# CV_Mode.net
KiCad netlist of a schematic drawn in Altium Designer
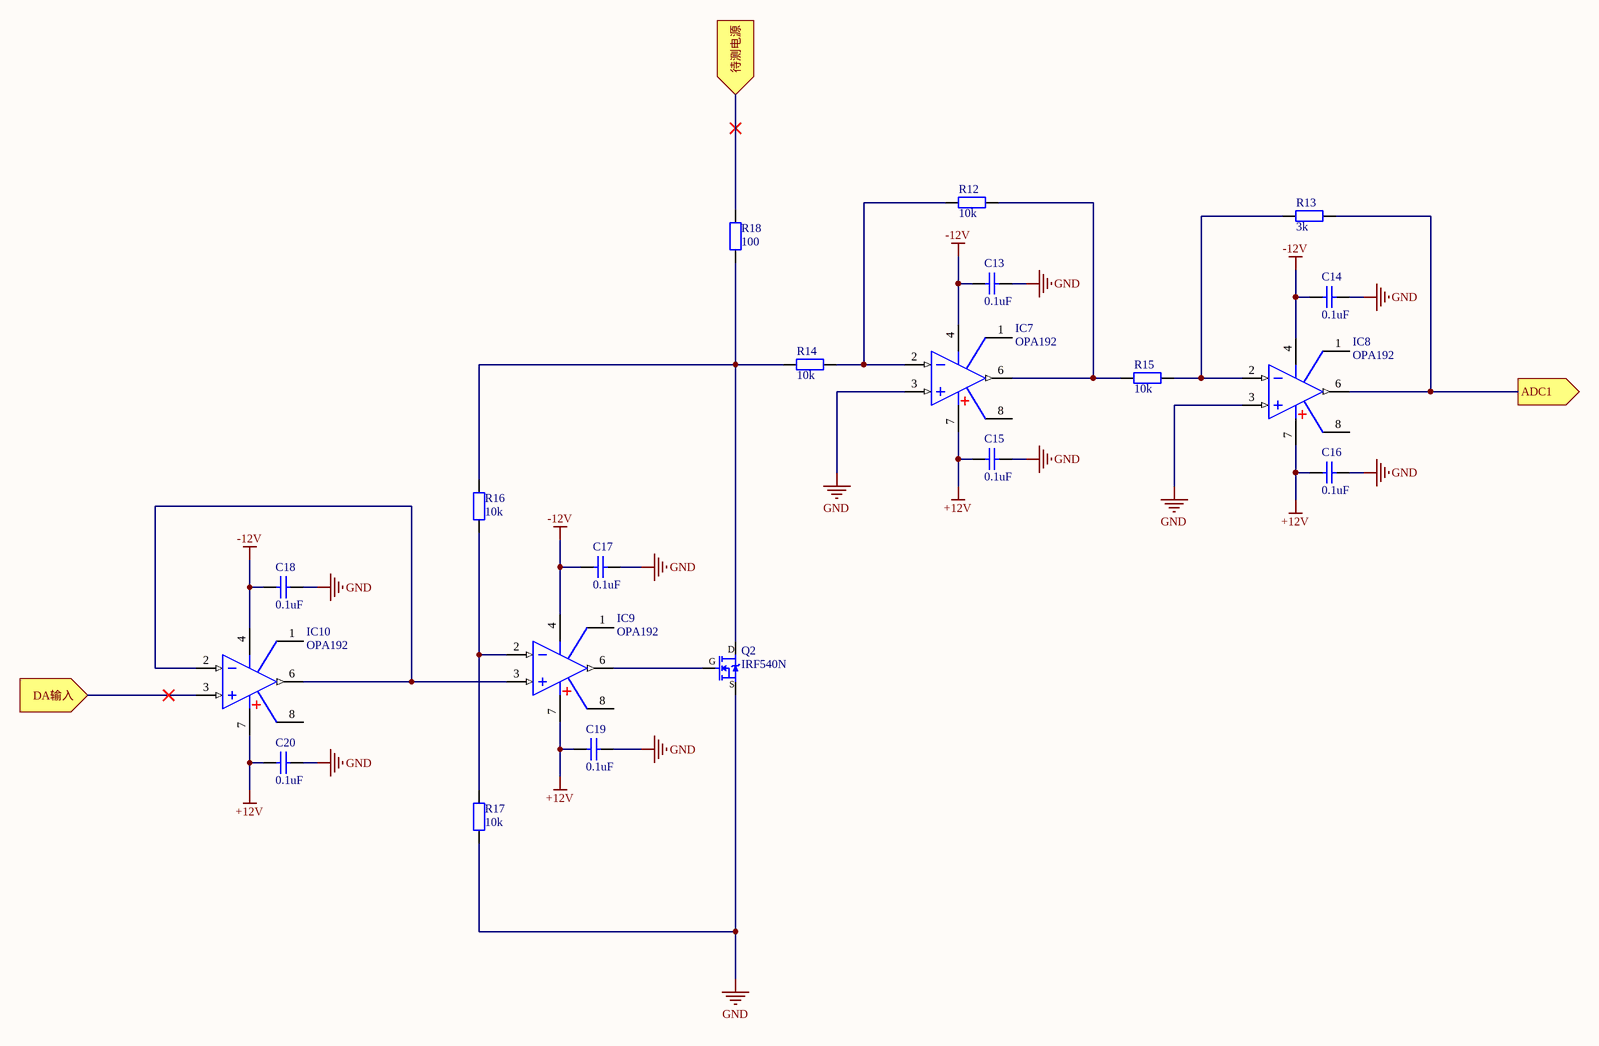
[diagram p0: CV_Mode.SchDoc]

(export (version "E")
  (design (tool "Eeschema 10.0.6"))
  (components
    (comp (ref "C13")
      (value "0.1uF")
      (footprint "瓷片电容")
      (description "直插电容")
      (fields (field (name "VOLTAGE") "63V") (field (name "PUBLISHER") "Altium Limited"))
      (libsource (lib "My_Intlib") (part "Cap_DIP"))
    )
    (comp (ref "C14")
      (value "0.1uF")
      (footprint "瓷片电容")
      (description "直插电容")
      (fields (field (name "VOLTAGE") "63V") (field (name "PUBLISHER") "Altium Limited"))
      (libsource (lib "My_Intlib") (part "Cap_DIP"))
    )
    (comp (ref "C15")
      (value "0.1uF")
      (footprint "瓷片电容")
      (description "直插电容")
      (fields (field (name "VOLTAGE") "63V") (field (name "PUBLISHER") "Altium Limited"))
      (libsource (lib "My_Intlib") (part "Cap_DIP"))
    )
    (comp (ref "C16")
      (value "0.1uF")
      (footprint "瓷片电容")
      (description "直插电容")
      (fields (field (name "VOLTAGE") "63V") (field (name "PUBLISHER") "Altium Limited"))
      (libsource (lib "My_Intlib") (part "Cap_DIP"))
    )
    (comp (ref "C17")
      (value "0.1uF")
      (footprint "瓷片电容")
      (description "直插电容")
      (fields (field (name "VOLTAGE") "63V") (field (name "PUBLISHER") "Altium Limited"))
      (libsource (lib "My_Intlib") (part "Cap_DIP"))
    )
    (comp (ref "C18")
      (value "0.1uF")
      (footprint "瓷片电容")
      (description "直插电容")
      (fields (field (name "VOLTAGE") "63V") (field (name "PUBLISHER") "Altium Limited"))
      (libsource (lib "My_Intlib") (part "Cap_DIP"))
    )
    (comp (ref "C19")
      (value "0.1uF")
      (footprint "瓷片电容")
      (description "直插电容")
      (fields (field (name "VOLTAGE") "63V") (field (name "PUBLISHER") "Altium Limited"))
      (libsource (lib "My_Intlib") (part "Cap_DIP"))
    )
    (comp (ref "C20")
      (value "0.1uF")
      (footprint "瓷片电容")
      (description "直插电容")
      (fields (field (name "VOLTAGE") "63V") (field (name "PUBLISHER") "Altium Limited"))
      (libsource (lib "My_Intlib") (part "Cap_DIP"))
    )
    (comp (ref "IC7")
      (value "OPA192")
      (footprint "SOP8_N")
      (description "High-Voltage, Rail-to-Rail Input/Output, 5µV, 0.2µV/˚C, Precision Operational Amplifier")
      (fields (field (name "版权归属") "源创客"))
      (libsource (lib "My_Intlib") (part "OPA192"))
    )
    (comp (ref "IC8")
      (value "OPA192")
      (footprint "SOP8_N")
      (description "High-Voltage, Rail-to-Rail Input/Output, 5µV, 0.2µV/˚C, Precision Operational Amplifier")
      (fields (field (name "版权归属") "源创客"))
      (libsource (lib "My_Intlib") (part "OPA192"))
    )
    (comp (ref "IC9")
      (value "OPA192")
      (footprint "SOP8_N")
      (description "High-Voltage, Rail-to-Rail Input/Output, 5µV, 0.2µV/˚C, Precision Operational Amplifier")
      (fields (field (name "版权归属") "源创客"))
      (libsource (lib "My_Intlib") (part "OPA192"))
    )
    (comp (ref "IC10")
      (value "OPA192")
      (footprint "SOP8_N")
      (description "High-Voltage, Rail-to-Rail Input/Output, 5µV, 0.2µV/˚C, Precision Operational Amplifier")
      (fields (field (name "版权归属") "源创客"))
      (libsource (lib "My_Intlib") (part "OPA192"))
    )
    (comp (ref "Q2")
      (value "IRF540N")
      (footprint "TO263-3B")
      (description "N沟场 100V/22A")
      (fields (field (name "版权归属") "源创客"))
      (libsource (lib "My_Intlib") (part "IRF540N"))
    )
    (comp (ref "R12")
      (value "10k")
      (footprint "RS 1/4W")
      (description "直插电阻")
      (libsource (lib "") (part "Res_DIP_1"))
    )
    (comp (ref "R13")
      (value "3k")
      (footprint "RS 1/4W")
      (description "直插电阻")
      (libsource (lib "") (part "Res_DIP_1"))
    )
    (comp (ref "R14")
      (value "10k")
      (footprint "RS 1/4W")
      (description "直插电阻")
      (libsource (lib "") (part "Res_DIP_1"))
    )
    (comp (ref "R15")
      (value "10k")
      (footprint "RS 1/4W")
      (description "直插电阻")
      (libsource (lib "") (part "Res_DIP_1"))
    )
    (comp (ref "R16")
      (value "10k")
      (footprint "RS 1/4W")
      (description "直插电阻")
      (libsource (lib "My_Intlib") (part "Res_DIP"))
    )
    (comp (ref "R17")
      (value "10k")
      (footprint "RS 1/4W")
      (description "直插电阻")
      (libsource (lib "My_Intlib") (part "Res_DIP"))
    )
    (comp (ref "R18")
      (value "100")
      (footprint "RS 1/4W")
      (description "直插电阻")
      (libsource (lib "My_Intlib") (part "Res_DIP"))
    )
  )
  (nets
    (net (code "1") (name "+12V") (class "Default")
      (node (ref "C15") (pin "1") (pinfunction "1_1") (pintype "passive"))
      (node (ref "C16") (pin "1") (pinfunction "1_1") (pintype "passive"))
      (node (ref "C19") (pin "1") (pinfunction "1_1") (pintype "passive"))
      (node (ref "C20") (pin "1") (pinfunction "1_1") (pintype "passive"))
      (node (ref "IC10") (pin "7") (pinfunction "V+_7") (pintype "power_in"))
      (node (ref "IC7") (pin "7") (pinfunction "V+_7") (pintype "power_in"))
      (node (ref "IC8") (pin "7") (pinfunction "V+_7") (pintype "power_in"))
      (node (ref "IC9") (pin "7") (pinfunction "V+_7") (pintype "power_in"))
    )
    (net (code "2") (name "-12V") (class "Default")
      (node (ref "C13") (pin "1") (pinfunction "1_1") (pintype "passive"))
      (node (ref "C14") (pin "1") (pinfunction "1_1") (pintype "passive"))
      (node (ref "C17") (pin "1") (pinfunction "1_1") (pintype "passive"))
      (node (ref "C18") (pin "1") (pinfunction "1_1") (pintype "passive"))
      (node (ref "IC10") (pin "4") (pinfunction "V-_4") (pintype "power_in"))
      (node (ref "IC7") (pin "4") (pinfunction "V-_4") (pintype "power_in"))
      (node (ref "IC8") (pin "4") (pinfunction "V-_4") (pintype "power_in"))
      (node (ref "IC9") (pin "4") (pinfunction "V-_4") (pintype "power_in"))
    )
    (net (code "3") (name "/ADC1") (class "Default")
      (node (ref "IC8") (pin "6") (pinfunction "OUT_6") (pintype "output"))
      (node (ref "R13") (pin "2") (pinfunction "2_2") (pintype "passive"))
    )
    (net (code "4") (name "/DA输入") (class "Default")
      (node (ref "IC10") (pin "3") (pinfunction "IN+_3") (pintype "input"))
    )
    (net (code "5") (name "/待测电源") (class "Default")
      (node (ref "R18") (pin "2") (pinfunction "2_2") (pintype "passive"))
    )
    (net (code "6") (name "GND") (class "Default")
      (node (ref "C13") (pin "2") (pinfunction "2_2") (pintype "passive"))
      (node (ref "C14") (pin "2") (pinfunction "2_2") (pintype "passive"))
      (node (ref "C15") (pin "2") (pinfunction "2_2") (pintype "passive"))
      (node (ref "C16") (pin "2") (pinfunction "2_2") (pintype "passive"))
      (node (ref "C17") (pin "2") (pinfunction "2_2") (pintype "passive"))
      (node (ref "C18") (pin "2") (pinfunction "2_2") (pintype "passive"))
      (node (ref "C19") (pin "2") (pinfunction "2_2") (pintype "passive"))
      (node (ref "C20") (pin "2") (pinfunction "2_2") (pintype "passive"))
      (node (ref "IC7") (pin "3") (pinfunction "IN+_3") (pintype "input"))
      (node (ref "IC8") (pin "3") (pinfunction "IN+_3") (pintype "input"))
      (node (ref "Q2") (pin "3") (pinfunction "D_3") (pintype "passive"))
      (node (ref "R17") (pin "1") (pinfunction "1_1") (pintype "passive"))
    )
    (net (code "7") (name "Net-(IC7-IN-)") (class "Default")
      (node (ref "IC7") (pin "2") (pinfunction "IN-_2") (pintype "input"))
      (node (ref "R12") (pin "1") (pinfunction "1_1") (pintype "passive"))
      (node (ref "R14") (pin "2") (pinfunction "2_2") (pintype "passive"))
    )
    (net (code "8") (name "Net-(IC7-OUT)") (class "Default")
      (node (ref "IC7") (pin "6") (pinfunction "OUT_6") (pintype "output"))
      (node (ref "R12") (pin "2") (pinfunction "2_2") (pintype "passive"))
      (node (ref "R15") (pin "1") (pinfunction "1_1") (pintype "passive"))
    )
    (net (code "9") (name "Net-(IC8-IN-)") (class "Default")
      (node (ref "IC8") (pin "2") (pinfunction "IN-_2") (pintype "input"))
      (node (ref "R13") (pin "1") (pinfunction "1_1") (pintype "passive"))
      (node (ref "R15") (pin "2") (pinfunction "2_2") (pintype "passive"))
    )
    (net (code "10") (name "Net-(IC9-IN-)") (class "Default")
      (node (ref "IC9") (pin "2") (pinfunction "IN-_2") (pintype "input"))
      (node (ref "R16") (pin "1") (pinfunction "1_1") (pintype "passive"))
      (node (ref "R17") (pin "2") (pinfunction "2_2") (pintype "passive"))
    )
    (net (code "11") (name "Net-(IC9-OUT)") (class "Default")
      (node (ref "IC9") (pin "6") (pinfunction "OUT_6") (pintype "output"))
      (node (ref "Q2") (pin "1") (pinfunction "G_1") (pintype "passive"))
    )
    (net (code "12") (name "Net-(IC10-IN-)") (class "Default")
      (node (ref "IC10") (pin "2") (pinfunction "IN-_2") (pintype "input"))
      (node (ref "IC10") (pin "6") (pinfunction "OUT_6") (pintype "output"))
      (node (ref "IC9") (pin "3") (pinfunction "IN+_3") (pintype "input"))
    )
    (net (code "13") (name "Net-(Q2-S)") (class "Default")
      (node (ref "Q2") (pin "2") (pinfunction "S_2") (pintype "passive"))
      (node (ref "R14") (pin "1") (pinfunction "1_1") (pintype "passive"))
      (node (ref "R16") (pin "2") (pinfunction "2_2") (pintype "passive"))
      (node (ref "R18") (pin "1") (pinfunction "1_1") (pintype "passive"))
    )
    (net (code "14") (name "unconnected-(IC7-Pad1)") (class "Default")
      (node (ref "IC7") (pin "1") (pinfunction "1_1") (pintype "passive"))
    )
    (net (code "15") (name "unconnected-(IC7-Pad8)") (class "Default")
      (node (ref "IC7") (pin "8") (pinfunction "8_8") (pintype "passive"))
    )
    (net (code "16") (name "unconnected-(IC8-Pad1)") (class "Default")
      (node (ref "IC8") (pin "1") (pinfunction "1_1") (pintype "passive"))
    )
    (net (code "17") (name "unconnected-(IC8-Pad8)") (class "Default")
      (node (ref "IC8") (pin "8") (pinfunction "8_8") (pintype "passive"))
    )
    (net (code "18") (name "unconnected-(IC9-Pad1)") (class "Default")
      (node (ref "IC9") (pin "1") (pinfunction "1_1") (pintype "passive"))
    )
    (net (code "19") (name "unconnected-(IC9-Pad8)") (class "Default")
      (node (ref "IC9") (pin "8") (pinfunction "8_8") (pintype "passive"))
    )
    (net (code "20") (name "unconnected-(IC10-Pad1)") (class "Default")
      (node (ref "IC10") (pin "1") (pinfunction "1_1") (pintype "passive"))
    )
    (net (code "21") (name "unconnected-(IC10-Pad8)") (class "Default")
      (node (ref "IC10") (pin "8") (pinfunction "8_8") (pintype "passive"))
    )
  )
)
